# RP2040.net
KiCad netlist of a schematic drawn in Altium Designer
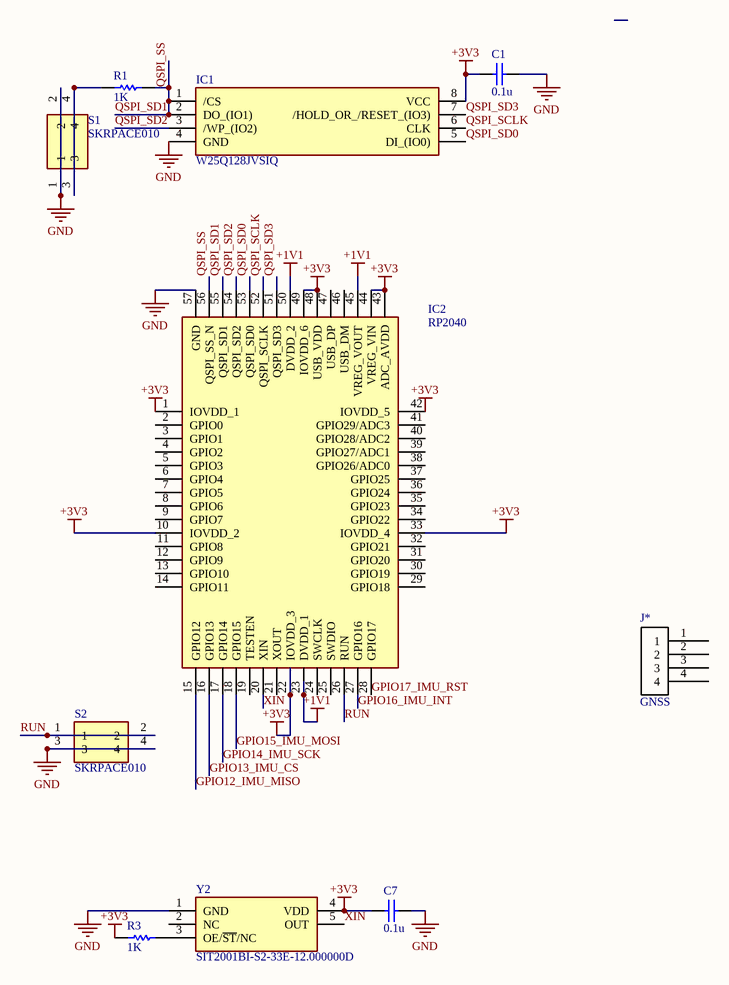
[diagram p0: RP2040.SchDoc]

(export (version "E")
  (design (tool "Eeschema 10.0.6"))
  (components
    (comp (ref "C1")
      (value "0.1u")
      (footprint "1608[0603]")
      (description "Capacitor")
      (libsource (lib "Simulation Generic Components") (part "Capacitor"))
    )
    (comp (ref "C7")
      (value "0.1u")
      (footprint "1608[0603]")
      (description "Capacitor")
      (libsource (lib "Simulation Generic Components") (part "Capacitor"))
    )
    (comp (ref "IC1")
      (value "W25Q128JVSIQ")
      (footprint "SamacSys:SOIC127P790X216-8N")
      (description "Integrated Circuit")
      (fields (field (name "MOUSER PART NUMBER") "454-W25Q128JVSIQ"))
      (libsource (lib "*") (part "W25Q128JVSIQ"))
    )
    (comp (ref "IC2")
      (value "RP2040")
      (footprint "SamacSys:QFN40P700X700X90-57N-D")
      (description "Integrated Circuit")
      (libsource (lib "*") (part "RP2040"))
    )
    (comp (ref "J*") (value "GNSS") (libsource (lib "tanekonsat_lib") (part "PinHeader_1.27_4_Half")))
    (comp (ref "R1")
      (value "1K")
      (footprint "1608[0603]")
      (description "Resistor")
      (libsource (lib "Simulation Generic Components") (part "Resistor"))
    )
    (comp (ref "R3")
      (value "1K")
      (footprint "1608[0603]")
      (description "Resistor")
      (libsource (lib "Simulation Generic Components") (part "Resistor"))
    )
    (comp (ref "S1")
      (value "SKRPACE010")
      (footprint "SamacSys:SMT(4.2X3.2)")
      (description "Switch")
      (fields (field (name "MOUSER PART NUMBER") "688-SKRPACE010"))
      (libsource (lib "") (part "SKRPACE010_1"))
    )
    (comp (ref "S2")
      (value "SKRPACE010")
      (footprint "SamacSys:SMT(4.2X3.2)")
      (description "Switch")
      (fields (field (name "MOUSER PART NUMBER") "688-SKRPACE010"))
      (libsource (lib "*") (part "SKRPACE010"))
    )
    (comp (ref "Y2")
      (value "SIT2001BI-S2-33E-12.000000D")
      (footprint "SamacSys:SOT95P280X145-5N")
      (description "Crystal or Oscillator")
      (libsource (lib "*") (part "SIT2001BI-S2-33E-12.000000D"))
    )
  )
  (nets
    (net (code "1") (name "+1V1") (class "Default")
      (node (ref "IC2") (pin "23") (pinfunction "DVDD_1_23") (pintype "passive"))
      (node (ref "IC2") (pin "45") (pinfunction "VREG_VOUT_45") (pintype "passive"))
      (node (ref "IC2") (pin "50") (pinfunction "DVDD_2_50") (pintype "passive"))
    )
    (net (code "2") (name "+3V3") (class "Default")
      (node (ref "C1") (pin "1") (pinfunction "1_1") (pintype "passive"))
      (node (ref "C7") (pin "1") (pinfunction "1_1") (pintype "passive"))
      (node (ref "IC1") (pin "8") (pinfunction "VCC_8") (pintype "passive"))
      (node (ref "IC2") (pin "1") (pinfunction "IOVDD_1_1") (pintype "passive"))
      (node (ref "IC2") (pin "10") (pinfunction "IOVDD_2_10") (pintype "passive"))
      (node (ref "IC2") (pin "22") (pinfunction "IOVDD_3_22") (pintype "passive"))
      (node (ref "IC2") (pin "33") (pinfunction "IOVDD_4_33") (pintype "passive"))
      (node (ref "IC2") (pin "42") (pinfunction "IOVDD_5_42") (pintype "passive"))
      (node (ref "IC2") (pin "43") (pinfunction "ADC_AVDD_43") (pintype "passive"))
      (node (ref "IC2") (pin "44") (pinfunction "VREG_VIN_44") (pintype "passive"))
      (node (ref "IC2") (pin "48") (pinfunction "USB_VDD_48") (pintype "passive"))
      (node (ref "IC2") (pin "49") (pinfunction "IOVDD_6_49") (pintype "passive"))
      (node (ref "R3") (pin "1") (pinfunction "1_1") (pintype "passive"))
      (node (ref "Y2") (pin "4") (pinfunction "VDD_4") (pintype "passive"))
    )
    (net (code "3") (name "/GPIO12_IMU_MISO") (class "Default")
      (node (ref "IC2") (pin "15") (pinfunction "GPIO12_15") (pintype "passive"))
    )
    (net (code "4") (name "/GPIO13_IMU_CS") (class "Default")
      (node (ref "IC2") (pin "16") (pinfunction "GPIO13_16") (pintype "passive"))
    )
    (net (code "5") (name "/GPIO14_IMU_SCK") (class "Default")
      (node (ref "IC2") (pin "17") (pinfunction "GPIO14_17") (pintype "passive"))
    )
    (net (code "6") (name "/GPIO15_IMU_MOSI") (class "Default")
      (node (ref "IC2") (pin "18") (pinfunction "GPIO15_18") (pintype "passive"))
    )
    (net (code "7") (name "/GPIO16_IMU_INT") (class "Default")
      (node (ref "IC2") (pin "27") (pinfunction "GPIO16_27") (pintype "passive"))
    )
    (net (code "8") (name "/GPIO17_IMU_RST") (class "Default")
      (node (ref "IC2") (pin "28") (pinfunction "GPIO17_28") (pintype "passive"))
    )
    (net (code "9") (name "/QSPI_SCLK") (class "Default")
      (node (ref "IC1") (pin "6") (pinfunction "CLK_6") (pintype "passive"))
      (node (ref "IC2") (pin "52") (pinfunction "QSPI_SCLK_52") (pintype "passive"))
    )
    (net (code "10") (name "/QSPI_SD0") (class "Default")
      (node (ref "IC1") (pin "5") (pinfunction "DI_(IO0)_5") (pintype "passive"))
      (node (ref "IC2") (pin "53") (pinfunction "QSPI_SD0_53") (pintype "passive"))
    )
    (net (code "11") (name "/QSPI_SD1") (class "Default")
      (node (ref "IC1") (pin "1") (pinfunction "/CS_1") (pintype "passive"))
      (node (ref "IC1") (pin "2") (pinfunction "DO_(IO1)_2") (pintype "passive"))
      (node (ref "IC2") (pin "55") (pinfunction "QSPI_SD1_55") (pintype "passive"))
      (node (ref "IC2") (pin "56") (pinfunction "QSPI_SS_N_56") (pintype "passive"))
      (node (ref "R1") (pin "2") (pinfunction "2_2") (pintype "passive"))
    )
    (net (code "12") (name "/QSPI_SD2") (class "Default")
      (node (ref "IC1") (pin "3") (pinfunction "/WP_(IO2)_3") (pintype "passive"))
      (node (ref "IC2") (pin "54") (pinfunction "QSPI_SD2_54") (pintype "passive"))
    )
    (net (code "13") (name "/QSPI_SD3") (class "Default")
      (node (ref "IC1") (pin "7") (pinfunction "/HOLD_OR_/RESET_(IO3)_7") (pintype "passive"))
      (node (ref "IC2") (pin "51") (pinfunction "QSPI_SD3_51") (pintype "passive"))
    )
    (net (code "14") (name "/RUN") (class "Default")
      (node (ref "IC2") (pin "26") (pinfunction "RUN_26") (pintype "passive"))
      (node (ref "S2") (pin "1") (pinfunction "1_1") (pintype "passive"))
      (node (ref "S2") (pin "2") (pinfunction "2_2") (pintype "passive"))
    )
    (net (code "15") (name "/XIN") (class "Default")
      (node (ref "IC2") (pin "20") (pinfunction "XIN_20") (pintype "passive"))
      (node (ref "Y2") (pin "5") (pinfunction "OUT_5") (pintype "passive"))
    )
    (net (code "16") (name "GND") (class "Default")
      (node (ref "C1") (pin "2") (pinfunction "2_2") (pintype "passive"))
      (node (ref "C7") (pin "2") (pinfunction "2_2") (pintype "passive"))
      (node (ref "IC1") (pin "4") (pinfunction "GND_4") (pintype "passive"))
      (node (ref "IC2") (pin "57") (pinfunction "GND_57") (pintype "passive"))
      (node (ref "S1") (pin "1") (pinfunction "1_1") (pintype "passive"))
      (node (ref "S1") (pin "2") (pinfunction "2_2") (pintype "passive"))
      (node (ref "S2") (pin "3") (pinfunction "3_3") (pintype "passive"))
      (node (ref "S2") (pin "4") (pinfunction "4_4") (pintype "passive"))
      (node (ref "Y2") (pin "1") (pinfunction "GND_1") (pintype "passive"))
    )
    (net (code "17") (name "Net-(R1-Pad1)") (class "Default")
      (node (ref "R1") (pin "1") (pinfunction "1_1") (pintype "passive"))
      (node (ref "S1") (pin "3") (pinfunction "3_3") (pintype "passive"))
      (node (ref "S1") (pin "4") (pinfunction "4_4") (pintype "passive"))
    )
    (net (code "18") (name "Net-(Y2-OE{slash}~{ST}{slash}NC)") (class "Default")
      (node (ref "R3") (pin "2") (pinfunction "2_2") (pintype "passive"))
      (node (ref "Y2") (pin "3") (pinfunction "OE/~{ST}/NC_3") (pintype "passive"))
    )
    (net (code "19") (name "unconnected-(IC2-GPIO0-Pad2)") (class "Default")
      (node (ref "IC2") (pin "2") (pinfunction "GPIO0_2") (pintype "passive"))
    )
    (net (code "20") (name "unconnected-(IC2-GPIO1-Pad3)") (class "Default")
      (node (ref "IC2") (pin "3") (pinfunction "GPIO1_3") (pintype "passive"))
    )
    (net (code "21") (name "unconnected-(IC2-GPIO2-Pad4)") (class "Default")
      (node (ref "IC2") (pin "4") (pinfunction "GPIO2_4") (pintype "passive"))
    )
    (net (code "22") (name "unconnected-(IC2-GPIO3-Pad5)") (class "Default")
      (node (ref "IC2") (pin "5") (pinfunction "GPIO3_5") (pintype "passive"))
    )
    (net (code "23") (name "unconnected-(IC2-GPIO4-Pad6)") (class "Default")
      (node (ref "IC2") (pin "6") (pinfunction "GPIO4_6") (pintype "passive"))
    )
    (net (code "24") (name "unconnected-(IC2-GPIO5-Pad7)") (class "Default")
      (node (ref "IC2") (pin "7") (pinfunction "GPIO5_7") (pintype "passive"))
    )
    (net (code "25") (name "unconnected-(IC2-GPIO6-Pad8)") (class "Default")
      (node (ref "IC2") (pin "8") (pinfunction "GPIO6_8") (pintype "passive"))
    )
    (net (code "26") (name "unconnected-(IC2-GPIO7-Pad9)") (class "Default")
      (node (ref "IC2") (pin "9") (pinfunction "GPIO7_9") (pintype "passive"))
    )
    (net (code "27") (name "unconnected-(IC2-GPIO8-Pad11)") (class "Default")
      (node (ref "IC2") (pin "11") (pinfunction "GPIO8_11") (pintype "passive"))
    )
    (net (code "28") (name "unconnected-(IC2-GPIO9-Pad12)") (class "Default")
      (node (ref "IC2") (pin "12") (pinfunction "GPIO9_12") (pintype "passive"))
    )
    (net (code "29") (name "unconnected-(IC2-GPIO10-Pad13)") (class "Default")
      (node (ref "IC2") (pin "13") (pinfunction "GPIO10_13") (pintype "passive"))
    )
    (net (code "30") (name "unconnected-(IC2-GPIO11-Pad14)") (class "Default")
      (node (ref "IC2") (pin "14") (pinfunction "GPIO11_14") (pintype "passive"))
    )
    (net (code "31") (name "unconnected-(IC2-GPIO18-Pad29)") (class "Default")
      (node (ref "IC2") (pin "29") (pinfunction "GPIO18_29") (pintype "passive"))
    )
    (net (code "32") (name "unconnected-(IC2-GPIO19-Pad30)") (class "Default")
      (node (ref "IC2") (pin "30") (pinfunction "GPIO19_30") (pintype "passive"))
    )
    (net (code "33") (name "unconnected-(IC2-GPIO20-Pad31)") (class "Default")
      (node (ref "IC2") (pin "31") (pinfunction "GPIO20_31") (pintype "passive"))
    )
    (net (code "34") (name "unconnected-(IC2-GPIO21-Pad32)") (class "Default")
      (node (ref "IC2") (pin "32") (pinfunction "GPIO21_32") (pintype "passive"))
    )
    (net (code "35") (name "unconnected-(IC2-GPIO22-Pad34)") (class "Default")
      (node (ref "IC2") (pin "34") (pinfunction "GPIO22_34") (pintype "passive"))
    )
    (net (code "36") (name "unconnected-(IC2-GPIO23-Pad35)") (class "Default")
      (node (ref "IC2") (pin "35") (pinfunction "GPIO23_35") (pintype "passive"))
    )
    (net (code "37") (name "unconnected-(IC2-GPIO24-Pad36)") (class "Default")
      (node (ref "IC2") (pin "36") (pinfunction "GPIO24_36") (pintype "passive"))
    )
    (net (code "38") (name "unconnected-(IC2-GPIO25-Pad37)") (class "Default")
      (node (ref "IC2") (pin "37") (pinfunction "GPIO25_37") (pintype "passive"))
    )
    (net (code "39") (name "unconnected-(IC2-GPIO26{slash}ADC0-Pad38)") (class "Default")
      (node (ref "IC2") (pin "38") (pinfunction "GPIO26/ADC0_38") (pintype "passive"))
    )
    (net (code "40") (name "unconnected-(IC2-GPIO27{slash}ADC1-Pad39)") (class "Default")
      (node (ref "IC2") (pin "39") (pinfunction "GPIO27/ADC1_39") (pintype "passive"))
    )
    (net (code "41") (name "unconnected-(IC2-GPIO28{slash}ADC2-Pad40)") (class "Default")
      (node (ref "IC2") (pin "40") (pinfunction "GPIO28/ADC2_40") (pintype "passive"))
    )
    (net (code "42") (name "unconnected-(IC2-GPIO29{slash}ADC3-Pad41)") (class "Default")
      (node (ref "IC2") (pin "41") (pinfunction "GPIO29/ADC3_41") (pintype "passive"))
    )
    (net (code "43") (name "unconnected-(IC2-SWCLK-Pad24)") (class "Default")
      (node (ref "IC2") (pin "24") (pinfunction "SWCLK_24") (pintype "passive"))
    )
    (net (code "44") (name "unconnected-(IC2-SWDIO-Pad25)") (class "Default")
      (node (ref "IC2") (pin "25") (pinfunction "SWDIO_25") (pintype "passive"))
    )
    (net (code "45") (name "unconnected-(IC2-TESTEN-Pad19)") (class "Default")
      (node (ref "IC2") (pin "19") (pinfunction "TESTEN_19") (pintype "passive"))
    )
    (net (code "46") (name "unconnected-(IC2-USB_DM-Pad46)") (class "Default")
      (node (ref "IC2") (pin "46") (pinfunction "USB_DM_46") (pintype "passive"))
    )
    (net (code "47") (name "unconnected-(IC2-USB_DP-Pad47)") (class "Default")
      (node (ref "IC2") (pin "47") (pinfunction "USB_DP_47") (pintype "passive"))
    )
    (net (code "48") (name "unconnected-(IC2-XOUT-Pad21)") (class "Default")
      (node (ref "IC2") (pin "21") (pinfunction "XOUT_21") (pintype "passive"))
    )
    (net (code "49") (name "unconnected-(J*-Pad1)") (class "Default")
      (node (ref "J*") (pin "1") (pinfunction "1_1") (pintype "passive"))
    )
    (net (code "50") (name "unconnected-(J*-Pad2)") (class "Default")
      (node (ref "J*") (pin "2") (pinfunction "2_2") (pintype "passive"))
    )
    (net (code "51") (name "unconnected-(J*-Pad3)") (class "Default")
      (node (ref "J*") (pin "3") (pinfunction "3_3") (pintype "passive"))
    )
    (net (code "52") (name "unconnected-(J*-Pad4)") (class "Default")
      (node (ref "J*") (pin "4") (pinfunction "4_4") (pintype "passive"))
    )
    (net (code "53") (name "unconnected-(Y2-NC-Pad2)") (class "Default")
      (node (ref "Y2") (pin "2") (pinfunction "NC_2") (pintype "passive"))
    )
  )
)
